# eagleExperiment2.net
KiCad netlist of a schematic drawn in EAGLE
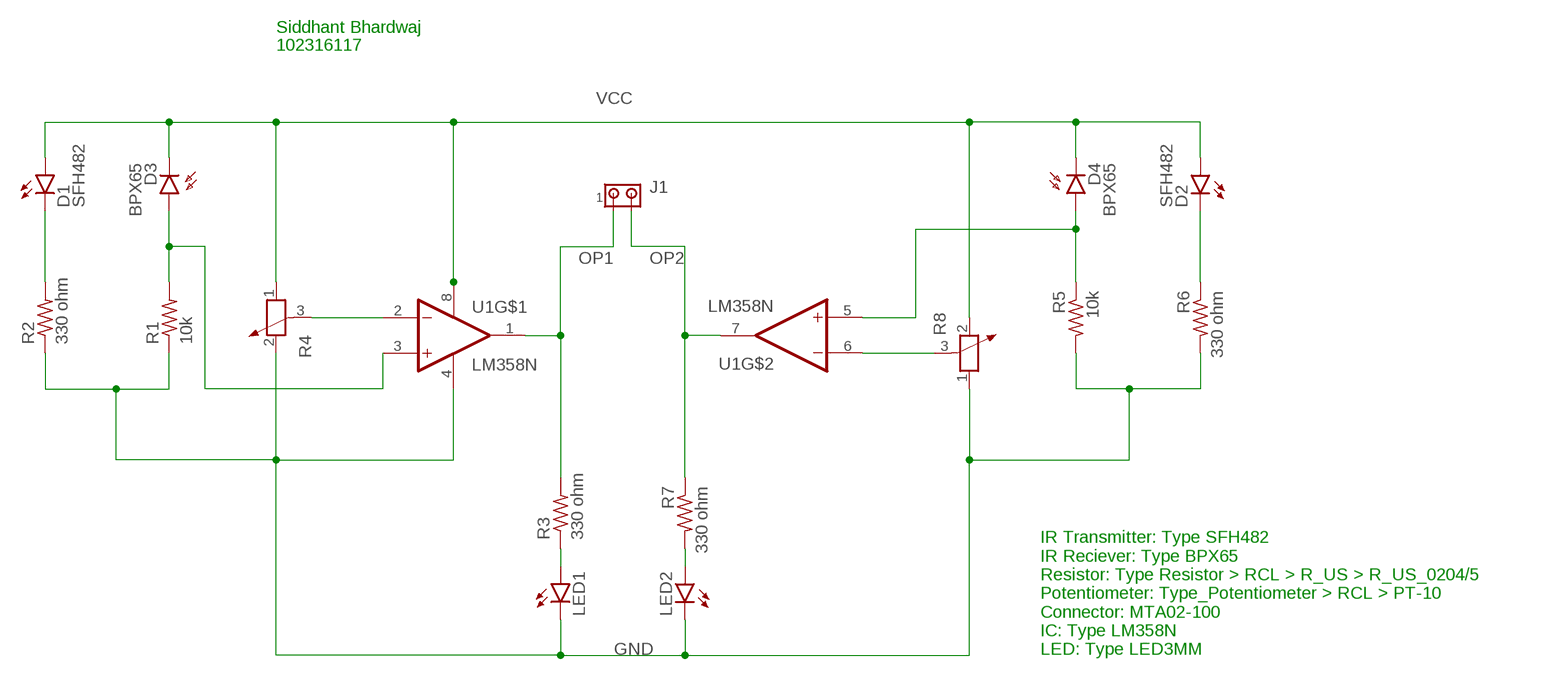
[diagram p0: schematic, sheet 1]

(export (version "E")
  (design (tool "Eeschema 10.0.6"))
  (components
    (comp (ref "D1")
      (value "SFH482")
      (footprint "eagle-import:SFH482")
      (libsource (lib "eagle-import") (part "SFH482"))
    )
    (comp (ref "D2")
      (value "SFH482")
      (footprint "eagle-import:SFH482")
      (libsource (lib "eagle-import") (part "SFH482"))
    )
    (comp (ref "D3")
      (value "BPX65")
      (footprint "eagle-import:BPX65")
      (fields (field (name "MPN") "BPX65."))
      (libsource (lib "eagle-import") (part "BPX65"))
    )
    (comp (ref "D4")
      (value "BPX65")
      (footprint "eagle-import:BPX65")
      (fields (field (name "MPN") "BPX65."))
      (libsource (lib "eagle-import") (part "BPX65"))
    )
    (comp (ref "J1")
      (value "MTA02-100")
      (footprint "eagle-import:10X02MTA")
      (libsource (lib "eagle-import") (part "MTA02-100"))
    )
    (comp (ref "LED1")
      (value "LED3MM")
      (footprint "eagle-import:LED3MM")
      (libsource (lib "eagle-import") (part "LED3MM"))
    )
    (comp (ref "LED2")
      (value "LED3MM")
      (footprint "eagle-import:LED3MM")
      (libsource (lib "eagle-import") (part "LED3MM"))
    )
    (comp (ref "R1")
      (value "10k")
      (footprint "eagle-import:0204_5")
      (libsource (lib "eagle-import") (part "R-US_0204/5"))
    )
    (comp (ref "R2")
      (value "330 ohm")
      (footprint "eagle-import:0204_5")
      (libsource (lib "eagle-import") (part "R-US_0204/5"))
    )
    (comp (ref "R3")
      (value "330 ohm")
      (footprint "eagle-import:0204_5")
      (libsource (lib "eagle-import") (part "R-US_0204/5"))
    )
    (comp (ref "R4")
      (value "POTENTIOMETER_PT-10")
      (footprint "eagle-import:PT-10")
      (libsource (lib "eagle-import") (part "POTENTIOMETER_PT-10"))
    )
    (comp (ref "R5")
      (value "10k")
      (footprint "eagle-import:0204_5")
      (libsource (lib "eagle-import") (part "R-US_0204/5"))
    )
    (comp (ref "R6")
      (value "330 ohm")
      (footprint "eagle-import:0204_5")
      (libsource (lib "eagle-import") (part "R-US_0204/5"))
    )
    (comp (ref "R7")
      (value "330 ohm")
      (footprint "eagle-import:0204_5")
      (libsource (lib "eagle-import") (part "R-US_0204/5"))
    )
    (comp (ref "R8")
      (value "POTENTIOMETER_PT-10")
      (footprint "eagle-import:PT-10")
      (libsource (lib "eagle-import") (part "POTENTIOMETER_PT-10"))
    )
    (comp (ref "U1")
      (value "LM358N")
      (footprint "eagle-import:DIP762W46P254L960H508Q8")
      (fields (field (name "MF") "Harris Corporation"))
      (libsource (lib "eagle-import") (part "LM358N"))
    )
  )
  (nets
    (net (code "1") (name "/GND") (class "Default")
      (node (ref "LED1") (pin "K") (pinfunction "C_K") (pintype "passive"))
      (node (ref "LED2") (pin "K") (pinfunction "C_K") (pintype "passive"))
      (node (ref "R1") (pin "1") (pinfunction "1_1") (pintype "passive"))
      (node (ref "R2") (pin "1") (pinfunction "1_1") (pintype "passive"))
      (node (ref "R4") (pin "2") (pinfunction "2_2") (pintype "passive"))
      (node (ref "R5") (pin "2") (pinfunction "2_2") (pintype "passive"))
      (node (ref "R6") (pin "2") (pinfunction "2_2") (pintype "passive"))
      (node (ref "R8") (pin "1") (pinfunction "1_1") (pintype "passive"))
      (node (ref "U1") (pin "4") (pinfunction "GND_4") (pintype "power_in"))
    )
    (net (code "2") (name "/OP1") (class "Default")
      (node (ref "J1") (pin "1") (pinfunction "1_1") (pintype "passive"))
      (node (ref "R3") (pin "2") (pinfunction "2_2") (pintype "passive"))
      (node (ref "U1") (pin "1") (pinfunction "1OUT_1") (pintype "output"))
    )
    (net (code "3") (name "/OP2") (class "Default")
      (node (ref "J1") (pin "2") (pinfunction "2_2") (pintype "passive"))
      (node (ref "R7") (pin "1") (pinfunction "1_1") (pintype "passive"))
      (node (ref "U1") (pin "7") (pinfunction "2OUT_7") (pintype "output"))
    )
    (net (code "4") (name "/VCC") (class "Default")
      (node (ref "D1") (pin "A") (pinfunction "A_A") (pintype "passive"))
      (node (ref "D2") (pin "A") (pinfunction "A_A") (pintype "passive"))
      (node (ref "D3") (pin "K") (pinfunction "C_K") (pintype "passive"))
      (node (ref "D4") (pin "K") (pinfunction "C_K") (pintype "passive"))
      (node (ref "R4") (pin "1") (pinfunction "1_1") (pintype "passive"))
      (node (ref "R8") (pin "2") (pinfunction "2_2") (pintype "passive"))
      (node (ref "U1") (pin "8") (pinfunction "VCC_8") (pintype "power_in"))
    )
    (net (code "5") (name "Net-(D1-C)") (class "Default")
      (node (ref "D1") (pin "K") (pinfunction "C_K") (pintype "passive"))
      (node (ref "R2") (pin "2") (pinfunction "2_2") (pintype "passive"))
    )
    (net (code "6") (name "Net-(D2-C)") (class "Default")
      (node (ref "D2") (pin "K") (pinfunction "C_K") (pintype "passive"))
      (node (ref "R6") (pin "1") (pinfunction "1_1") (pintype "passive"))
    )
    (net (code "7") (name "Net-(LED1-PadA)") (class "Default")
      (node (ref "LED1") (pin "A") (pinfunction "A_A") (pintype "passive"))
      (node (ref "R3") (pin "1") (pinfunction "1_1") (pintype "passive"))
    )
    (net (code "8") (name "Net-(LED2-PadA)") (class "Default")
      (node (ref "LED2") (pin "A") (pinfunction "A_A") (pintype "passive"))
      (node (ref "R7") (pin "2") (pinfunction "2_2") (pintype "passive"))
    )
    (net (code "9") (name "Net-(U1A-1IN+)") (class "Default")
      (node (ref "D3") (pin "A") (pinfunction "A_A") (pintype "passive"))
      (node (ref "R1") (pin "2") (pinfunction "2_2") (pintype "passive"))
      (node (ref "U1") (pin "3") (pinfunction "1IN+_3") (pintype "input"))
    )
    (net (code "10") (name "Net-(U1A-1IN-)") (class "Default")
      (node (ref "R4") (pin "3") (pinfunction "3_3") (pintype "passive"))
      (node (ref "U1") (pin "2") (pinfunction "1IN-_2") (pintype "input"))
    )
    (net (code "11") (name "Net-(U1B-2IN+)") (class "Default")
      (node (ref "D4") (pin "A") (pinfunction "A_A") (pintype "passive"))
      (node (ref "R5") (pin "1") (pinfunction "1_1") (pintype "passive"))
      (node (ref "U1") (pin "5") (pinfunction "2IN+_5") (pintype "input"))
    )
    (net (code "12") (name "Net-(U1B-2IN-)") (class "Default")
      (node (ref "R8") (pin "3") (pinfunction "3_3") (pintype "passive"))
      (node (ref "U1") (pin "6") (pinfunction "2IN-_6") (pintype "input"))
    )
  )
)
